# Power_Board.net
KiCad netlist of a schematic drawn in EAGLE
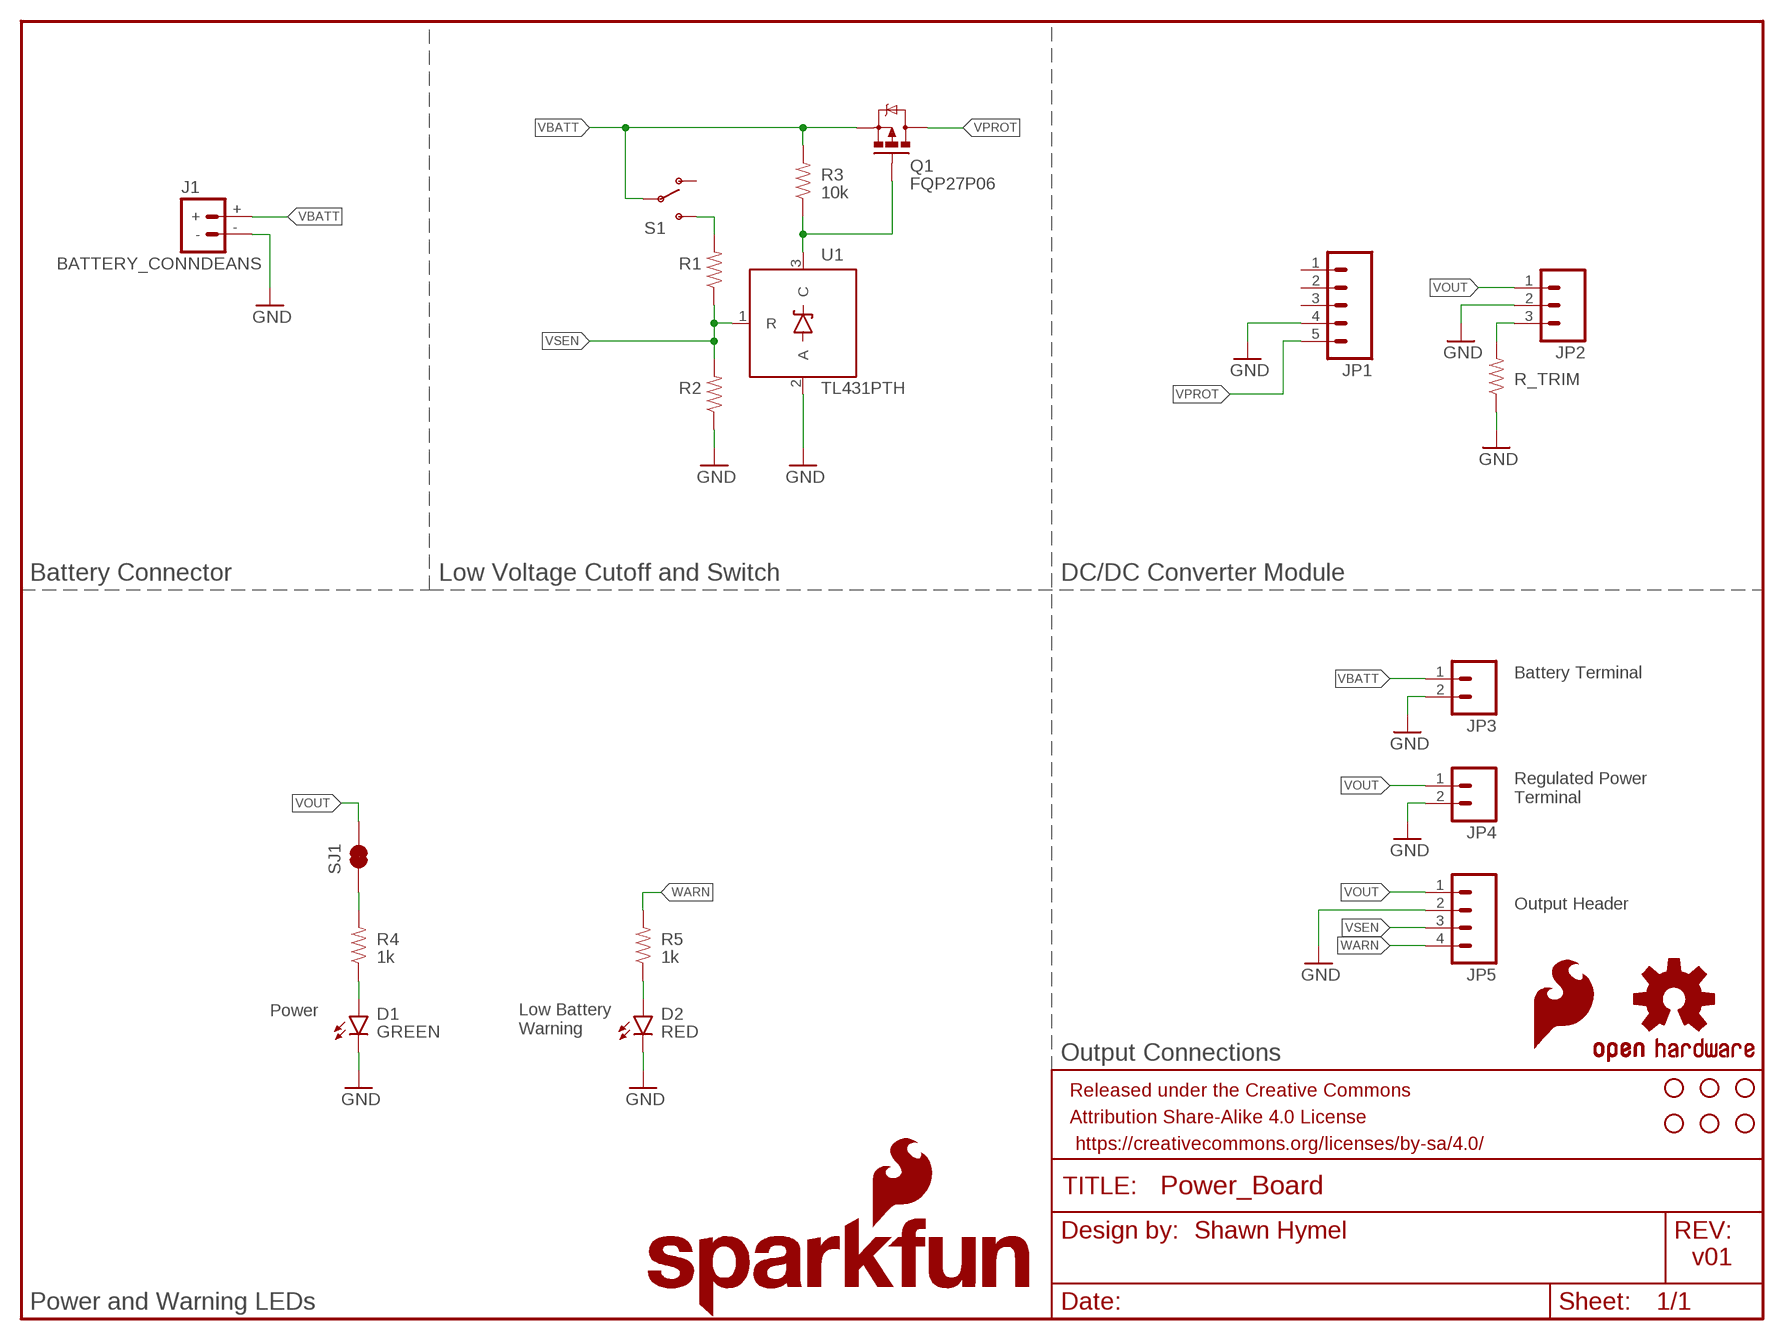
[diagram p0: schematic, sheet 1]

(export (version "E")
  (design (tool "Eeschema 10.0.6"))
  (components
    (comp (ref "D1")
      (value "GREEN")
      (footprint "eagle-import:LED5MM")
      (libsource (lib "eagle-import") (part "LED5MM"))
    )
    (comp (ref "D2")
      (value "RED")
      (footprint "eagle-import:LED5MM")
      (libsource (lib "eagle-import") (part "LED5MM"))
    )
    (comp (ref "FRAME1")
      (value "FRAME-LETTER")
      (footprint "eagle-import:CREATIVE_COMMONS")
      (fields
        (field (name "DESIGNER") "NAME")
        (field (name "VERSION") "v01")
        (field (name "DESIGNER_1") "Shawn Hymel")
      )
      (libsource (lib "eagle-import") (part "FRAME-LETTER"))
    )
    (comp (ref "J1")
      (value "BATTERY_CONNDEANS")
      (footprint "eagle-import:DEANS")
      (libsource (lib "eagle-import") (part "BATTERY_CONNDEANS"))
    )
    (comp (ref "JP1")
      (value "M05LOCK")
      (footprint "eagle-import:1X05_LOCK")
      (libsource (lib "eagle-import") (part "M05LOCK"))
    )
    (comp (ref "JP2")
      (value "M03LOCK")
      (footprint "eagle-import:1X03_LOCK")
      (libsource (lib "eagle-import") (part "M03LOCK"))
    )
    (comp (ref "JP3")
      (value "M025MM")
      (footprint "eagle-import:SCREWTERMINAL-5MM-2")
      (libsource (lib "eagle-import") (part "M025MM"))
    )
    (comp (ref "JP4")
      (value "M025MM")
      (footprint "eagle-import:SCREWTERMINAL-5MM-2")
      (libsource (lib "eagle-import") (part "M025MM"))
    )
    (comp (ref "JP5")
      (value "M04LOCK")
      (footprint "eagle-import:1X04_LOCK")
      (libsource (lib "eagle-import") (part "M04LOCK"))
    )
    (comp (ref "LOGO1")
      (value "OSHW-LOGOS")
      (footprint "eagle-import:OSHW-LOGO-S")
      (libsource (lib "eagle-import") (part "OSHW-LOGOS"))
    )
    (comp (ref "LOGO2")
      (value "SFE_LOGO_FLAME.1_INCH")
      (footprint "eagle-import:SFE_LOGO_FLAME_.1")
      (libsource (lib "eagle-import") (part "SFE_LOGO_FLAME.1_INCH"))
    )
    (comp (ref "LOGO3")
      (value "SFE_LOGO_NAME_FLAME.2_INCH")
      (footprint "eagle-import:SFE_LOGO_NAME_FLAME_.2")
      (libsource (lib "eagle-import") (part "SFE_LOGO_NAME_FLAME.2_INCH"))
    )
    (comp (ref "Q1")
      (value "MOSFET-PCHANNELFQP27P06")
      (footprint "eagle-import:TO220V")
      (fields (field (name "PART_NAME") "FQP27P06"))
      (libsource (lib "eagle-import") (part "MOSFET-PCHANNELFQP27P06"))
    )
    (comp (ref "R1")
      (value "RESISTORPTH-1/4W")
      (footprint "eagle-import:AXIAL-0.4")
      (libsource (lib "eagle-import") (part "RESISTORPTH-1/4W"))
    )
    (comp (ref "R2")
      (value "RESISTORPTH-1/4W")
      (footprint "eagle-import:AXIAL-0.4")
      (libsource (lib "eagle-import") (part "RESISTORPTH-1/4W"))
    )
    (comp (ref "R3")
      (value "RESISTORPTH-1/4W")
      (footprint "eagle-import:AXIAL-0.4")
      (libsource (lib "eagle-import") (part "RESISTORPTH-1/4W"))
    )
    (comp (ref "R4")
      (value "RESISTORPTH-1/4W")
      (footprint "eagle-import:AXIAL-0.4")
      (libsource (lib "eagle-import") (part "RESISTORPTH-1/4W"))
    )
    (comp (ref "R5")
      (value "RESISTORPTH-1/4W")
      (footprint "eagle-import:AXIAL-0.4")
      (libsource (lib "eagle-import") (part "RESISTORPTH-1/4W"))
    )
    (comp (ref "R_TRIM")
      (value "RESISTORPTH-1/4W")
      (footprint "eagle-import:AXIAL-0.4")
      (libsource (lib "eagle-import") (part "RESISTORPTH-1/4W"))
    )
    (comp (ref "S1")
      (value "SWITCH-SPDTPTH")
      (footprint "eagle-import:SWITCH-SPDT")
      (libsource (lib "eagle-import") (part "SWITCH-SPDTPTH"))
    )
    (comp (ref "SJ1")
      (value "JUMPER-PAD-2-NC_BY_TRACE")
      (footprint "eagle-import:PAD-JUMPER-2-NC_BY_TRACE_YES_SILK")
      (libsource (lib "eagle-import") (part "JUMPER-PAD-2-NC_BY_TRACE"))
    )
    (comp (ref "STANDOFF1")
      (value "STAND-OFF")
      (footprint "eagle-import:STAND-OFF")
      (libsource (lib "eagle-import") (part "STAND-OFF"))
    )
    (comp (ref "STANDOFF2")
      (value "STAND-OFF")
      (footprint "eagle-import:STAND-OFF")
      (libsource (lib "eagle-import") (part "STAND-OFF"))
    )
    (comp (ref "STANDOFF3")
      (value "STAND-OFF")
      (footprint "eagle-import:STAND-OFF")
      (libsource (lib "eagle-import") (part "STAND-OFF"))
    )
    (comp (ref "STANDOFF4")
      (value "STAND-OFF")
      (footprint "eagle-import:STAND-OFF")
      (libsource (lib "eagle-import") (part "STAND-OFF"))
    )
    (comp (ref "STANDOFF5")
      (value "STAND-OFF")
      (footprint "eagle-import:STAND-OFF")
      (libsource (lib "eagle-import") (part "STAND-OFF"))
    )
    (comp (ref "STANDOFF6")
      (value "STAND-OFF")
      (footprint "eagle-import:STAND-OFF")
      (libsource (lib "eagle-import") (part "STAND-OFF"))
    )
    (comp (ref "U1")
      (value "TL431PTH")
      (footprint "eagle-import:TO-92")
      (libsource (lib "eagle-import") (part "TL431PTH"))
    )
  )
  (nets
    (net (code "1") (name "GND") (class "Default")
      (node (ref "D1") (pin "K") (pinfunction "C_K") (pintype "passive"))
      (node (ref "D2") (pin "K") (pinfunction "C_K") (pintype "passive"))
      (node (ref "J1") (pin "-") (pinfunction "-_-") (pintype "passive"))
      (node (ref "JP1") (pin "4") (pinfunction "4_4") (pintype "passive"))
      (node (ref "JP2") (pin "2") (pinfunction "2_2") (pintype "passive"))
      (node (ref "JP3") (pin "2") (pinfunction "2_2") (pintype "passive"))
      (node (ref "JP4") (pin "2") (pinfunction "2_2") (pintype "passive"))
      (node (ref "JP5") (pin "2") (pinfunction "2_2") (pintype "passive"))
      (node (ref "R2") (pin "P$1") (pinfunction "1_P$1") (pintype "passive"))
      (node (ref "R_TRIM") (pin "P$1") (pinfunction "1_P$1") (pintype "passive"))
      (node (ref "U1") (pin "2") (pinfunction "A_2") (pintype "bidirectional"))
    )
    (net (code "2") (name "Net-(Q1-G)") (class "Default")
      (node (ref "Q1") (pin "1") (pinfunction "G_1") (pintype "passive"))
      (node (ref "R3") (pin "P$1") (pinfunction "1_P$1") (pintype "passive"))
      (node (ref "U1") (pin "3") (pinfunction "C_3") (pintype "bidirectional"))
    )
    (net (code "3") (name "Net-(R1-2)") (class "Default")
      (node (ref "R1") (pin "P$2") (pinfunction "2_P$2") (pintype "passive"))
      (node (ref "S1") (pin "3") (pinfunction "S_3") (pintype "passive"))
    )
    (net (code "4") (name "Net-(R4-1)") (class "Default")
      (node (ref "D1") (pin "A") (pinfunction "A_A") (pintype "passive"))
      (node (ref "R4") (pin "P$1") (pinfunction "1_P$1") (pintype "passive"))
    )
    (net (code "5") (name "Net-(R4-2)") (class "Default")
      (node (ref "R4") (pin "P$2") (pinfunction "2_P$2") (pintype "passive"))
      (node (ref "SJ1") (pin "1") (pinfunction "1_1") (pintype "passive"))
    )
    (net (code "6") (name "Net-(R5-1)") (class "Default")
      (node (ref "D2") (pin "A") (pinfunction "A_A") (pintype "passive"))
      (node (ref "R5") (pin "P$1") (pinfunction "1_P$1") (pintype "passive"))
    )
    (net (code "7") (name "Net-(R_TRIM-2)") (class "Default")
      (node (ref "JP2") (pin "3") (pinfunction "3_3") (pintype "passive"))
      (node (ref "R_TRIM") (pin "P$2") (pinfunction "2_P$2") (pintype "passive"))
    )
    (net (code "8") (name "VBATT") (class "Default")
      (node (ref "J1") (pin "+") (pinfunction "+_+") (pintype "passive"))
      (node (ref "JP3") (pin "1") (pinfunction "1_1") (pintype "passive"))
      (node (ref "Q1") (pin "3") (pinfunction "S_3") (pintype "passive"))
      (node (ref "R3") (pin "P$2") (pinfunction "2_P$2") (pintype "passive"))
      (node (ref "S1") (pin "2") (pinfunction "P_2") (pintype "passive"))
    )
    (net (code "9") (name "VOUT") (class "Default")
      (node (ref "JP2") (pin "1") (pinfunction "1_1") (pintype "passive"))
      (node (ref "JP4") (pin "1") (pinfunction "1_1") (pintype "passive"))
      (node (ref "JP5") (pin "1") (pinfunction "1_1") (pintype "passive"))
      (node (ref "SJ1") (pin "2") (pinfunction "2_2") (pintype "passive"))
    )
    (net (code "10") (name "VPROT") (class "Default")
      (node (ref "JP1") (pin "5") (pinfunction "5_5") (pintype "passive"))
      (node (ref "Q1") (pin "2") (pinfunction "D_2") (pintype "passive"))
    )
    (net (code "11") (name "VSEN") (class "Default")
      (node (ref "JP5") (pin "3") (pinfunction "3_3") (pintype "passive"))
      (node (ref "R1") (pin "P$1") (pinfunction "1_P$1") (pintype "passive"))
      (node (ref "R2") (pin "P$2") (pinfunction "2_P$2") (pintype "passive"))
      (node (ref "U1") (pin "1") (pinfunction "R_1") (pintype "bidirectional"))
    )
    (net (code "12") (name "WARN") (class "Default")
      (node (ref "JP5") (pin "4") (pinfunction "4_4") (pintype "passive"))
      (node (ref "R5") (pin "P$2") (pinfunction "2_P$2") (pintype "passive"))
    )
    (net (code "13") (name "unconnected-(JP1-Pad1)") (class "Default")
      (node (ref "JP1") (pin "1") (pinfunction "1_1") (pintype "passive"))
    )
    (net (code "14") (name "unconnected-(JP1-Pad2)") (class "Default")
      (node (ref "JP1") (pin "2") (pinfunction "2_2") (pintype "passive"))
    )
    (net (code "15") (name "unconnected-(JP1-Pad3)") (class "Default")
      (node (ref "JP1") (pin "3") (pinfunction "3_3") (pintype "passive"))
    )
    (net (code "16") (name "unconnected-(S1-O-Pad1)") (class "Default")
      (node (ref "S1") (pin "1") (pinfunction "O_1") (pintype "passive"))
    )
  )
)
